# ph.net
KiCad netlist of a schematic drawn in Altium Designer
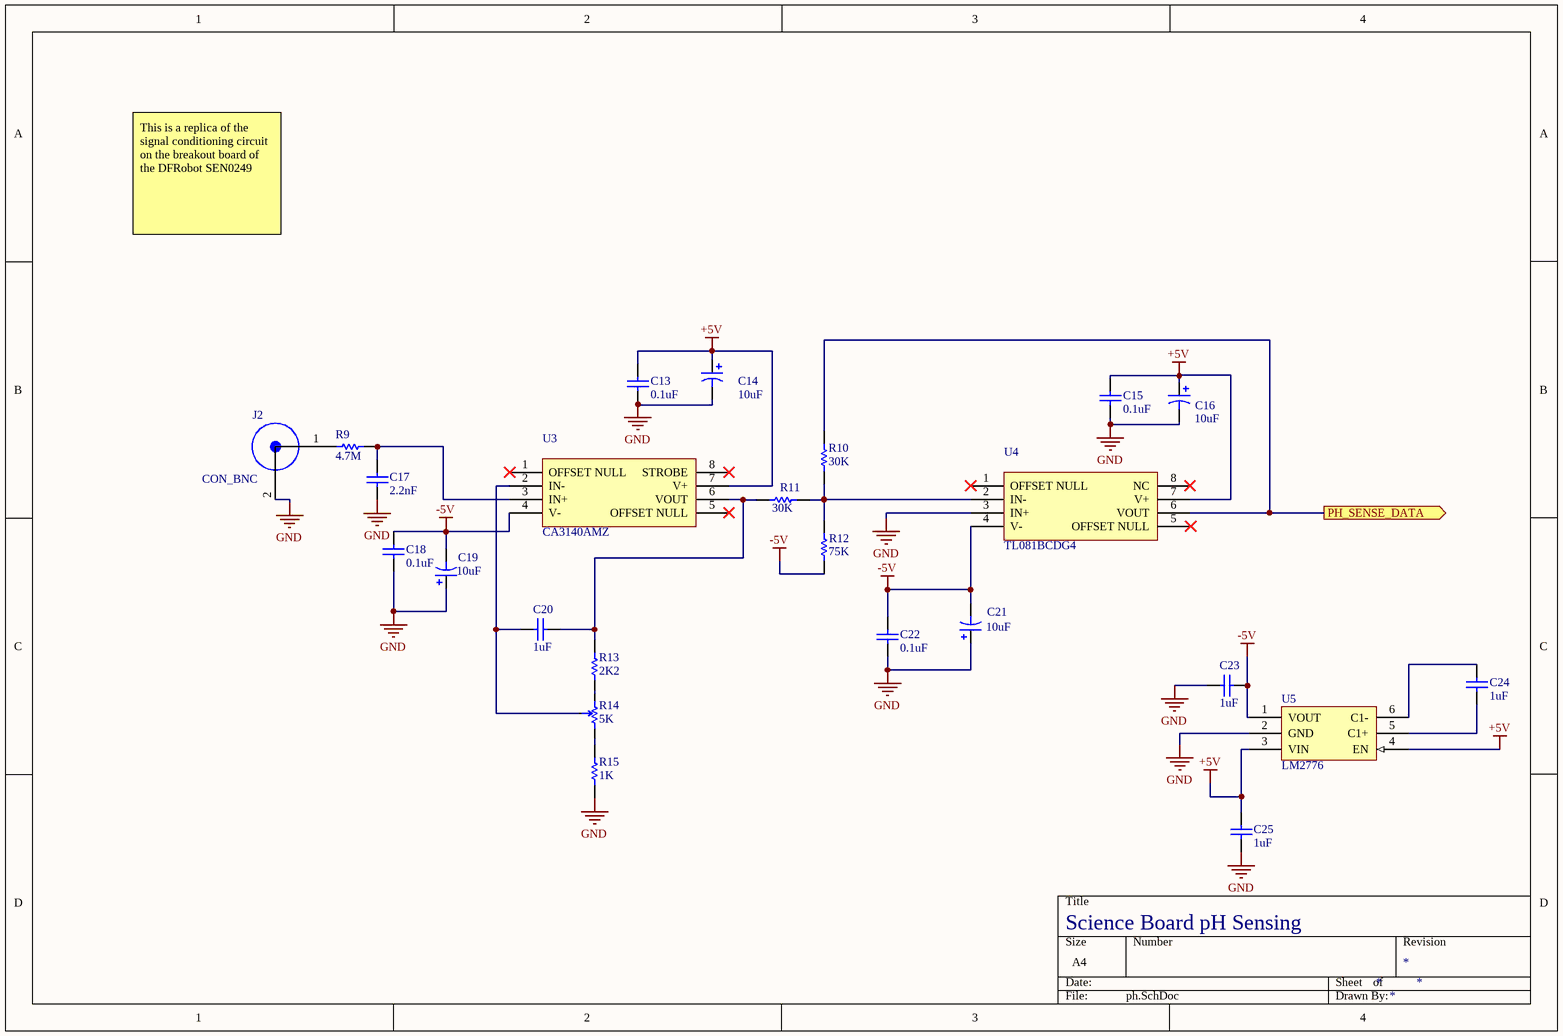
[diagram p0: ph.SchDoc]

(export (version "E")
  (design (tool "Eeschema 10.0.6"))
  (components
    (comp (ref "C13")
      (value "0.1uF")
      (footprint "CAPC0603(1608)55_N")
      (description "CAP CER 0.1UF 50V X7R 0603")
      (fields (field (name "PART NUMBER") "GCM188R71H104KA57D") (field (name "MANUFACTURER") "Yageo"))
      (libsource (lib "UWRT_Schematic_Library_2019") (part "CAP_0.1uF_50V_0603"))
    )
    (comp (ref "C14")
      (value "10uF")
      (footprint "AVX-CAPC3528_V")
      (description "Capacitor, Tantalum, 10uF 10% 20V MCCT-B (3528)")
      (fields (field (name "PART NUMBER") "CC0603MRX5R6BB106") (field (name "MANUFACTURER") "Yageo"))
      (libsource (lib "UWRT_Schematic_Library_2019") (part "CAP_10uF_0603_POL"))
    )
    (comp (ref "C15")
      (value "0.1uF")
      (footprint "CAPC0603(1608)55_N")
      (description "CAP CER 0.1UF 50V X7R 0603")
      (fields (field (name "PART NUMBER") "GCM188R71H104KA57D") (field (name "MANUFACTURER") "Yageo"))
      (libsource (lib "UWRT_Schematic_Library_2019") (part "CAP_0.1uF_50V_0603"))
    )
    (comp (ref "C16")
      (value "10uF")
      (footprint "AVX-CAPC3528_V")
      (description "Capacitor, Tantalum, 10uF 10% 20V MCCT-B (3528)")
      (fields (field (name "PART NUMBER") "CC0603MRX5R6BB106") (field (name "MANUFACTURER") "Yageo"))
      (libsource (lib "UWRT_Schematic_Library_2019") (part "CAP_10uF_0603_POL"))
    )
    (comp (ref "C17")
      (value "2.2nF")
      (footprint "CAPC0603(1608)55_N")
      (description "CAP CER 2.2NF 25V X7R 0603")
      (fields (field (name "PART NUMBER") "CC0603KRX7R8BB222") (field (name "MANUFACTURER") "Yageo"))
      (libsource (lib "UWRT_Schematic_Library_2019") (part "CAP_2.2nF_0603"))
    )
    (comp (ref "C18")
      (value "0.1uF")
      (footprint "CAPC0603(1608)55_N")
      (description "CAP CER 0.1UF 50V X7R 0603")
      (fields (field (name "PART NUMBER") "GCM188R71H104KA57D") (field (name "MANUFACTURER") "Yageo"))
      (libsource (lib "UWRT_Schematic_Library_2019") (part "CAP_0.1uF_50V_0603"))
    )
    (comp (ref "C19")
      (value "10uF")
      (footprint "AVX-CAPC3528_V")
      (description "Capacitor, Tantalum, 10uF 10% 20V MCCT-B (3528)")
      (fields (field (name "PART NUMBER") "CC0603MRX5R6BB106") (field (name "MANUFACTURER") "Yageo"))
      (libsource (lib "UWRT_Schematic_Library_2019") (part "CAP_10uF_0603_POL"))
    )
    (comp (ref "C20")
      (value "1uF")
      (footprint "CAPC0603(1608)55_N")
      (description "CAP CER 1UF 16V Y5V 0603")
      (fields (field (name "PART NUMBER") "CC0603ZRY5V7BB105") (field (name "MANUFACTURER") "Yageo"))
      (libsource (lib "UWRT_Schematic_Library_2019") (part "CAP_1uF_16V_0603"))
    )
    (comp (ref "C21")
      (value "10uF")
      (footprint "AVX-CAPC3528_V")
      (description "Capacitor, Tantalum, 10uF 10% 20V MCCT-B (3528)")
      (fields (field (name "PART NUMBER") "CC0603MRX5R6BB106") (field (name "MANUFACTURER") "Yageo"))
      (libsource (lib "UWRT_Schematic_Library_2019") (part "CAP_10uF_0603_POL"))
    )
    (comp (ref "C22")
      (value "0.1uF")
      (footprint "CAPC0603(1608)55_N")
      (description "CAP CER 0.1UF 50V X7R 0603")
      (fields (field (name "PART NUMBER") "GCM188R71H104KA57D") (field (name "MANUFACTURER") "Yageo"))
      (libsource (lib "UWRT_Schematic_Library_2019") (part "CAP_0.1uF_50V_0603"))
    )
    (comp (ref "C23")
      (value "1uF")
      (footprint "CAPC0603(1608)55_N")
      (description "CAP CER 1UF 16V Y5V 0603")
      (fields (field (name "PART NUMBER") "CC0603ZRY5V7BB105") (field (name "MANUFACTURER") "Yageo"))
      (libsource (lib "UWRT_Schematic_Library_2019") (part "CAP_1uF_16V_0603"))
    )
    (comp (ref "C24")
      (value "1uF")
      (footprint "CAPC0603(1608)55_N")
      (description "CAP CER 1UF 16V Y5V 0603")
      (fields (field (name "PART NUMBER") "CC0603ZRY5V7BB105") (field (name "MANUFACTURER") "Yageo"))
      (libsource (lib "UWRT_Schematic_Library_2019") (part "CAP_1uF_16V_0603"))
    )
    (comp (ref "C25")
      (value "1uF")
      (footprint "CAPC0603(1608)55_N")
      (description "CAP CER 1UF 16V Y5V 0603")
      (fields (field (name "PART NUMBER") "CC0603ZRY5V7BB105") (field (name "MANUFACTURER") "Yageo"))
      (libsource (lib "UWRT_Schematic_Library_2019") (part "CAP_1uF_16V_0603"))
    )
    (comp (ref "J2")
      (value "CON_BNC")
      (footprint "1-1337543-0")
      (fields (field (name "MANUFACTURER") "TE Connectivity"))
      (libsource (lib "UWRT_Schematic_Library_2019") (part "CON_BNC"))
    )
    (comp (ref "R9")
      (value "4.7M")
      (footprint "RESC0603(1608)_N")
      (description "RES SMD 4.7M OHM 1% 1/10W 0603")
      (fields (field (name "TOLERANCE") "1%") (field (name "MANUFACTURER") "Yageo"))
      (libsource (lib "UWRT_Schematic_Library_2019") (part "RES_4M7_0603"))
    )
    (comp (ref "R10")
      (value "30K")
      (footprint "RESC0603(1608)_N")
      (description "RES SMD 30K OHM 0.5% 1/10W 0603")
      (fields (field (name "MANUFACTURER") "Yageo") (field (name "TOLERANCE") "0.5%"))
      (libsource (lib "UWRT_Schematic_Library_2019") (part "RES_30K_0603"))
    )
    (comp (ref "R11")
      (value "30K")
      (footprint "RESC0603(1608)_N")
      (description "RES SMD 30K OHM 0.5% 1/10W 0603")
      (fields (field (name "MANUFACTURER") "Yageo") (field (name "TOLERANCE") "0.5%"))
      (libsource (lib "UWRT_Schematic_Library_2019") (part "RES_30K_0603"))
    )
    (comp (ref "R12")
      (value "75K")
      (footprint "RESC0603(1608)_N")
      (description "RES SMD 75K OHM 0.5% 1/10W 0603")
      (fields (field (name "MANUFACTURER") "Yageo") (field (name "TOLERANCE") "0.5%"))
      (libsource (lib "UWRT_Schematic_Library_2019") (part "RES_75K_0603"))
    )
    (comp (ref "R13")
      (value "2K2")
      (footprint "RESC0603(1608)_N")
      (description "RES SMD 2.2K OHM 1% 1/10W 0603")
      (fields (field (name "MANUFACTURER") "Yageo") (field (name "TOLERANCE") "1%"))
      (libsource (lib "UWRT_Schematic_Library_2019") (part "RES_2K2_0603"))
    )
    (comp (ref "R14")
      (value "5K")
      (footprint "3362P-1-502LF")
      (description "TRIMMER 5K OHM 0.5W PC PIN TOP")
      (fields (field (name "MANUFACTURER") "Bourns Inc.") (field (name "TOLERANCE") "10%"))
      (libsource (lib "UWRT_Schematic_Library_2019") (part "POT_5K"))
    )
    (comp (ref "R15")
      (value "1K")
      (footprint "RESC0603(1608)_N")
      (description "RES SMD 1K OHM 5% 1/10W 0603")
      (fields (field (name "TOLERANCE") "5%") (field (name "MANUFACTURER") "Yageo"))
      (libsource (lib "UWRT_Schematic_Library_2019") (part "RES_1K_0603"))
    )
    (comp (ref "U3")
      (value "CA3140AMZ")
      (footprint "CA3140AMZ")
      (description "4.5MHz, BiMOS Operational Amplifier with MOSFET Input/Bipolar Output")
      (libsource (lib "UWRT_Schematic_Library_2019") (part "CA3140AMZ"))
    )
    (comp (ref "U4")
      (value "TL081BCDG4")
      (footprint "TL081BCDG4")
      (description "IC OPAMP JFET 3MHZ 8SOIC")
      (libsource (lib "UWRT_Schematic_Library_2019") (part "TL081BCDG4"))
    )
    (comp (ref "U5")
      (value "LM2776")
      (footprint "SOT23-6")
      (description "LM2776 Switched Capacitor Inverter")
      (libsource (lib "UWRT_Schematic_Library_2019") (part "LM2776"))
    )
  )
  (nets
    (net (code "1") (name "+5V") (class "Default")
      (node (ref "C13") (pin "2") (pinfunction "2_2") (pintype "passive"))
      (node (ref "C14") (pin "1") (pinfunction "1_1") (pintype "passive"))
      (node (ref "C15") (pin "2") (pinfunction "2_2") (pintype "passive"))
      (node (ref "C16") (pin "1") (pinfunction "1_1") (pintype "passive"))
      (node (ref "C25") (pin "2") (pinfunction "2_2") (pintype "passive"))
      (node (ref "U3") (pin "7") (pinfunction "V+_7") (pintype "passive"))
      (node (ref "U4") (pin "7") (pinfunction "V+_7") (pintype "passive"))
      (node (ref "U5") (pin "3") (pinfunction "VIN_3") (pintype "power_in"))
      (node (ref "U5") (pin "4") (pinfunction "EN_4") (pintype "input"))
    )
    (net (code "2") (name "-5V") (class "Default")
      (node (ref "C18") (pin "2") (pinfunction "2_2") (pintype "passive"))
      (node (ref "C19") (pin "2") (pinfunction "2_2") (pintype "passive"))
      (node (ref "C21") (pin "2") (pinfunction "2_2") (pintype "passive"))
      (node (ref "C22") (pin "2") (pinfunction "2_2") (pintype "passive"))
      (node (ref "C23") (pin "1") (pinfunction "1_1") (pintype "passive"))
      (node (ref "R12") (pin "1") (pinfunction "1_1") (pintype "passive"))
      (node (ref "U3") (pin "4") (pinfunction "V-_4") (pintype "passive"))
      (node (ref "U4") (pin "4") (pinfunction "V-_4") (pintype "passive"))
      (node (ref "U5") (pin "1") (pinfunction "VOUT_1") (pintype "power_in"))
    )
    (net (code "3") (name "/PH_SENSE_DATA") (class "Default")
      (node (ref "R10") (pin "2") (pinfunction "2_2") (pintype "passive"))
      (node (ref "U4") (pin "6") (pinfunction "VOUT_6") (pintype "passive"))
    )
    (net (code "4") (name "GND") (class "Default")
      (node (ref "C13") (pin "1") (pinfunction "1_1") (pintype "passive"))
      (node (ref "C14") (pin "2") (pinfunction "2_2") (pintype "passive"))
      (node (ref "C15") (pin "1") (pinfunction "1_1") (pintype "passive"))
      (node (ref "C16") (pin "2") (pinfunction "2_2") (pintype "passive"))
      (node (ref "C17") (pin "1") (pinfunction "1_1") (pintype "passive"))
      (node (ref "C18") (pin "1") (pinfunction "1_1") (pintype "passive"))
      (node (ref "C19") (pin "1") (pinfunction "1_1") (pintype "passive"))
      (node (ref "C21") (pin "1") (pinfunction "1_1") (pintype "passive"))
      (node (ref "C22") (pin "1") (pinfunction "1_1") (pintype "passive"))
      (node (ref "C23") (pin "2") (pinfunction "2_2") (pintype "passive"))
      (node (ref "C25") (pin "1") (pinfunction "1_1") (pintype "passive"))
      (node (ref "J2") (pin "2") (pintype "passive"))
      (node (ref "R15") (pin "1") (pinfunction "1_1") (pintype "passive"))
      (node (ref "U4") (pin "3") (pinfunction "IN+_3") (pintype "passive"))
      (node (ref "U5") (pin "2") (pinfunction "GND_2") (pintype "passive"))
    )
    (net (code "5") (name "Net-(J2-Pad1)") (class "Default")
      (node (ref "J2") (pin "1") (pintype "passive"))
      (node (ref "R9") (pin "1") (pinfunction "1_1") (pintype "passive"))
    )
    (net (code "6") (name "Net-(R13-Pad1)") (class "Default")
      (node (ref "R13") (pin "1") (pinfunction "1_1") (pintype "passive"))
      (node (ref "R14") (pin "1") (pinfunction "1_1") (pintype "passive"))
    )
    (net (code "7") (name "Net-(R14-Pad2)") (class "Default")
      (node (ref "R14") (pin "2") (pinfunction "2_2") (pintype "passive"))
      (node (ref "R15") (pin "2") (pinfunction "2_2") (pintype "passive"))
    )
    (net (code "8") (name "Net-(U3-IN+)") (class "Default")
      (node (ref "C17") (pin "2") (pinfunction "2_2") (pintype "passive"))
      (node (ref "R9") (pin "2") (pinfunction "2_2") (pintype "passive"))
      (node (ref "U3") (pin "3") (pinfunction "IN+_3") (pintype "passive"))
    )
    (net (code "9") (name "Net-(U3-IN-)") (class "Default")
      (node (ref "C20") (pin "1") (pinfunction "1_1") (pintype "passive"))
      (node (ref "R14") (pin "3") (pinfunction "3_3") (pintype "passive"))
      (node (ref "U3") (pin "2") (pinfunction "IN-_2") (pintype "passive"))
    )
    (net (code "10") (name "Net-(U3-VOUT)") (class "Default")
      (node (ref "C20") (pin "2") (pinfunction "2_2") (pintype "passive"))
      (node (ref "R11") (pin "1") (pinfunction "1_1") (pintype "passive"))
      (node (ref "R13") (pin "2") (pinfunction "2_2") (pintype "passive"))
      (node (ref "U3") (pin "6") (pinfunction "VOUT_6") (pintype "passive"))
    )
    (net (code "11") (name "Net-(U4-IN-)") (class "Default")
      (node (ref "R10") (pin "1") (pinfunction "1_1") (pintype "passive"))
      (node (ref "R11") (pin "2") (pinfunction "2_2") (pintype "passive"))
      (node (ref "R12") (pin "2") (pinfunction "2_2") (pintype "passive"))
      (node (ref "U4") (pin "2") (pinfunction "IN-_2") (pintype "passive"))
    )
    (net (code "12") (name "Net-(U5-C1+)") (class "Default")
      (node (ref "C24") (pin "1") (pinfunction "1_1") (pintype "passive"))
      (node (ref "U5") (pin "5") (pinfunction "C1+_5") (pintype "power_in"))
    )
    (net (code "13") (name "Net-(U5-C1-)") (class "Default")
      (node (ref "C24") (pin "2") (pinfunction "2_2") (pintype "passive"))
      (node (ref "U5") (pin "6") (pinfunction "C1-_6") (pintype "power_in"))
    )
    (net (code "14") (name "unconnected-(U3-OFFSET_NULL-Pad1)") (class "Default")
      (node (ref "U3") (pin "1") (pinfunction "OFFSET_NULL_1") (pintype "passive"))
    )
    (net (code "15") (name "unconnected-(U3-OFFSET_NULL-Pad5)") (class "Default")
      (node (ref "U3") (pin "5") (pinfunction "OFFSET_NULL_5") (pintype "passive+no_connect"))
    )
    (net (code "16") (name "unconnected-(U3-STROBE-Pad8)") (class "Default")
      (node (ref "U3") (pin "8") (pinfunction "STROBE_8") (pintype "passive+no_connect"))
    )
    (net (code "17") (name "unconnected-(U4-NC-Pad8)") (class "Default")
      (node (ref "U4") (pin "8") (pinfunction "NC_8") (pintype "passive"))
    )
    (net (code "18") (name "unconnected-(U4-OFFSET_NULL-Pad1)") (class "Default")
      (node (ref "U4") (pin "1") (pinfunction "OFFSET_NULL_1") (pintype "passive+no_connect"))
    )
    (net (code "19") (name "unconnected-(U4-OFFSET_NULL-Pad5)") (class "Default")
      (node (ref "U4") (pin "5") (pinfunction "OFFSET_NULL_5") (pintype "passive"))
    )
  )
)
